# Main.net
KiCad netlist of a schematic drawn in Altium Designer
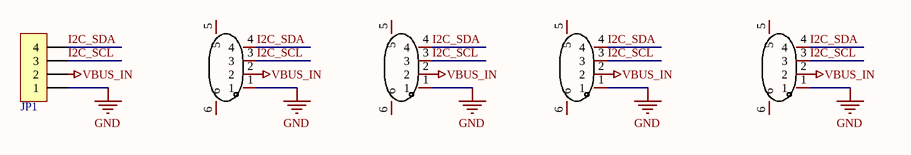
[diagram p0: Main.SchDoc]

(export (version "E")
  (design (tool "Eeschema 10.0.6"))
  (components
    (comp (ref "FPC2")
      (value "0.5K-DX-4PWB")
      (footprint "FPC-SMD_4P-P0.50_DEALON_0.5K-DX-4PWB")
      (fields (field (name "MANUFACTURER") "HDGC(华德共创)"))
      (libsource (lib "altium-import") (part "root_2_0.5K-DX-4PWB_"))
    )
    (comp (ref "FPC3")
      (value "0.5K-DX-4PWB")
      (footprint "FPC-SMD_4P-P0.50_DEALON_0.5K-DX-4PWB")
      (fields (field (name "MANUFACTURER") "HDGC(华德共创)"))
      (libsource (lib "altium-import") (part "root_2_0.5K-DX-4PWB_"))
    )
    (comp (ref "FPC4")
      (value "0.5K-DX-4PWB")
      (footprint "FPC-SMD_4P-P0.50_DEALON_0.5K-DX-4PWB")
      (fields (field (name "MANUFACTURER") "HDGC(华德共创)"))
      (libsource (lib "altium-import") (part "root_2_0.5K-DX-4PWB_"))
    )
    (comp (ref "FPC5")
      (value "0.5K-DX-4PWB")
      (footprint "FPC-SMD_4P-P0.50_DEALON_0.5K-DX-4PWB")
      (fields (field (name "MANUFACTURER") "HDGC(华德共创)"))
      (libsource (lib "altium-import") (part "root_2_0.5K-DX-4PWB_"))
    )
    (comp (ref "JP1")
      (value "HDR-1X4")
      (footprint "HDR1.27-LI-4P")
      (description "4P连接器")
      (libsource (lib "5.2 - 1.27mm连接器(1.27排针排母)") (part "Header 4"))
    )
  )
  (nets
    (net (code "1") (name "/I2C_SCL") (class "Default")
      (node (ref "FPC2") (pin "3") (pinfunction "3_3") (pintype "passive"))
      (node (ref "FPC3") (pin "3") (pinfunction "3_3") (pintype "passive"))
      (node (ref "FPC4") (pin "3") (pinfunction "3_3") (pintype "passive"))
      (node (ref "FPC5") (pin "3") (pinfunction "3_3") (pintype "passive"))
      (node (ref "JP1") (pin "3") (pinfunction "3_3") (pintype "passive"))
    )
    (net (code "2") (name "/I2C_SDA") (class "Default")
      (node (ref "FPC2") (pin "4") (pinfunction "4_4") (pintype "passive"))
      (node (ref "FPC3") (pin "4") (pinfunction "4_4") (pintype "passive"))
      (node (ref "FPC4") (pin "4") (pinfunction "4_4") (pintype "passive"))
      (node (ref "FPC5") (pin "4") (pinfunction "4_4") (pintype "passive"))
      (node (ref "JP1") (pin "4") (pinfunction "4_4") (pintype "passive"))
    )
    (net (code "3") (name "GND") (class "Default")
      (node (ref "FPC2") (pin "1") (pinfunction "1_1") (pintype "passive"))
      (node (ref "FPC3") (pin "1") (pinfunction "1_1") (pintype "passive"))
      (node (ref "FPC4") (pin "1") (pinfunction "1_1") (pintype "passive"))
      (node (ref "FPC5") (pin "1") (pinfunction "1_1") (pintype "passive"))
      (node (ref "JP1") (pin "1") (pinfunction "1_1") (pintype "passive"))
    )
    (net (code "4") (name "VBUS_IN") (class "Default")
      (node (ref "FPC2") (pin "2") (pinfunction "2_2") (pintype "passive"))
      (node (ref "FPC3") (pin "2") (pinfunction "2_2") (pintype "passive"))
      (node (ref "FPC4") (pin "2") (pinfunction "2_2") (pintype "passive"))
      (node (ref "FPC5") (pin "2") (pinfunction "2_2") (pintype "passive"))
      (node (ref "JP1") (pin "2") (pinfunction "2_2") (pintype "passive"))
    )
    (net (code "5") (name "unconnected-(FPC2-Pad5)") (class "Default")
      (node (ref "FPC2") (pin "5") (pinfunction "5_5") (pintype "passive"))
    )
    (net (code "6") (name "unconnected-(FPC2-Pad6)") (class "Default")
      (node (ref "FPC2") (pin "6") (pinfunction "6_6") (pintype "passive"))
    )
    (net (code "7") (name "unconnected-(FPC3-Pad5)") (class "Default")
      (node (ref "FPC3") (pin "5") (pinfunction "5_5") (pintype "passive"))
    )
    (net (code "8") (name "unconnected-(FPC3-Pad6)") (class "Default")
      (node (ref "FPC3") (pin "6") (pinfunction "6_6") (pintype "passive"))
    )
    (net (code "9") (name "unconnected-(FPC4-Pad5)") (class "Default")
      (node (ref "FPC4") (pin "5") (pinfunction "5_5") (pintype "passive"))
    )
    (net (code "10") (name "unconnected-(FPC4-Pad6)") (class "Default")
      (node (ref "FPC4") (pin "6") (pinfunction "6_6") (pintype "passive"))
    )
    (net (code "11") (name "unconnected-(FPC5-Pad5)") (class "Default")
      (node (ref "FPC5") (pin "5") (pinfunction "5_5") (pintype "passive"))
    )
    (net (code "12") (name "unconnected-(FPC5-Pad6)") (class "Default")
      (node (ref "FPC5") (pin "6") (pinfunction "6_6") (pintype "passive"))
    )
  )
)
